# CurvedThumbs.net
KiCad netlist of a schematic drawn in EAGLE
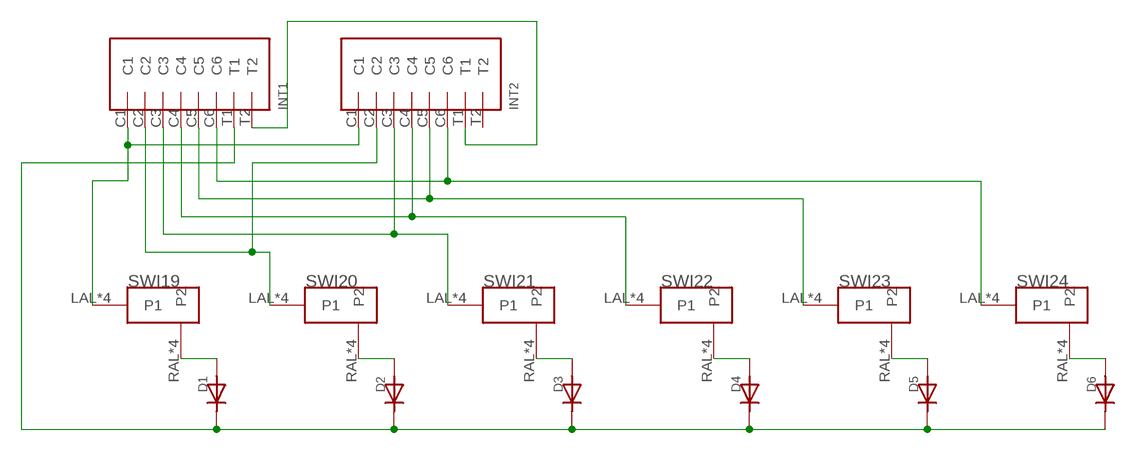
[diagram p0: schematic, sheet 1]

(export (version "E")
  (design (tool "Eeschema 10.0.6"))
  (components
    (comp (ref "D1")
      (value "DIODE")
      (footprint "eagle-import:DIODE_COMBO")
      (libsource (lib "eagle-import") (part "DIODE"))
    )
    (comp (ref "D2")
      (value "DIODE")
      (footprint "eagle-import:DIODE_COMBO")
      (libsource (lib "eagle-import") (part "DIODE"))
    )
    (comp (ref "D3")
      (value "DIODE")
      (footprint "eagle-import:DIODE_COMBO")
      (libsource (lib "eagle-import") (part "DIODE"))
    )
    (comp (ref "D4")
      (value "DIODE")
      (footprint "eagle-import:DIODE_COMBO")
      (libsource (lib "eagle-import") (part "DIODE"))
    )
    (comp (ref "D5")
      (value "DIODE")
      (footprint "eagle-import:DIODE_COMBO")
      (libsource (lib "eagle-import") (part "DIODE"))
    )
    (comp (ref "D6")
      (value "DIODE")
      (footprint "eagle-import:DIODE_COMBO")
      (libsource (lib "eagle-import") (part "DIODE"))
    )
    (comp (ref "INT1")
      (value "INTRCNNT")
      (footprint "eagle-import:INTRCNNT")
      (libsource (lib "eagle-import") (part "INTRCNNT"))
    )
    (comp (ref "INT2")
      (value "INTRCNNT")
      (footprint "eagle-import:INTRCNNT")
      (libsource (lib "eagle-import") (part "INTRCNNT"))
    )
    (comp (ref "SWI19")
      (value "MX/ALPSDOUBLESIDED")
      (footprint "eagle-import:DOUBLED_MX_ALPS")
      (libsource (lib "eagle-import") (part "MX/ALPSDOUBLESIDED"))
    )
    (comp (ref "SWI20")
      (value "MX/ALPSDOUBLESIDED")
      (footprint "eagle-import:DOUBLED_MX_ALPS")
      (libsource (lib "eagle-import") (part "MX/ALPSDOUBLESIDED"))
    )
    (comp (ref "SWI21")
      (value "MX/ALPSDOUBLESIDED")
      (footprint "eagle-import:DOUBLED_MX_ALPS")
      (libsource (lib "eagle-import") (part "MX/ALPSDOUBLESIDED"))
    )
    (comp (ref "SWI22")
      (value "MX/ALPSDOUBLESIDED")
      (footprint "eagle-import:DOUBLED_MX_ALPS")
      (libsource (lib "eagle-import") (part "MX/ALPSDOUBLESIDED"))
    )
    (comp (ref "SWI23")
      (value "MX/ALPSDOUBLESIDED")
      (footprint "eagle-import:DOUBLED_MX_ALPS")
      (libsource (lib "eagle-import") (part "MX/ALPSDOUBLESIDED"))
    )
    (comp (ref "SWI24")
      (value "MX/ALPSDOUBLESIDED")
      (footprint "eagle-import:DOUBLED_MX_ALPS")
      (libsource (lib "eagle-import") (part "MX/ALPSDOUBLESIDED"))
    )
  )
  (nets
    (net (code "1") (name "Net-(D1-AN-PadANOSB)") (class "Default")
      (node (ref "D1") (pin "ANOSB") (pinfunction "AN_ANOSB") (pintype "bidirectional"))
      (node (ref "D1") (pin "ANOST") (pinfunction "AN_ANOST") (pintype "bidirectional"))
      (node (ref "D1") (pin "ANOT") (pinfunction "AN_ANOT") (pintype "bidirectional"))
      (node (ref "SWI19") (pin "RAL") (pinfunction "P2_RAL") (pintype "bidirectional"))
      (node (ref "SWI19") (pin "RAR") (pinfunction "P2_RAR") (pintype "bidirectional"))
      (node (ref "SWI19") (pin "RCL") (pinfunction "P2_RCL") (pintype "bidirectional"))
      (node (ref "SWI19") (pin "RCR") (pinfunction "P2_RCR") (pintype "bidirectional"))
    )
    (net (code "2") (name "Net-(D1-CAT-PadCATSB)") (class "Default")
      (node (ref "D1") (pin "CATSB") (pinfunction "CAT_CATSB") (pintype "bidirectional"))
      (node (ref "D1") (pin "CATST") (pinfunction "CAT_CATST") (pintype "bidirectional"))
      (node (ref "D1") (pin "CATT") (pinfunction "CAT_CATT") (pintype "bidirectional"))
      (node (ref "D2") (pin "CATSB") (pinfunction "CAT_CATSB") (pintype "bidirectional"))
      (node (ref "D2") (pin "CATST") (pinfunction "CAT_CATST") (pintype "bidirectional"))
      (node (ref "D2") (pin "CATT") (pinfunction "CAT_CATT") (pintype "bidirectional"))
      (node (ref "D3") (pin "CATSB") (pinfunction "CAT_CATSB") (pintype "bidirectional"))
      (node (ref "D3") (pin "CATST") (pinfunction "CAT_CATST") (pintype "bidirectional"))
      (node (ref "D3") (pin "CATT") (pinfunction "CAT_CATT") (pintype "bidirectional"))
      (node (ref "D4") (pin "CATSB") (pinfunction "CAT_CATSB") (pintype "bidirectional"))
      (node (ref "D4") (pin "CATST") (pinfunction "CAT_CATST") (pintype "bidirectional"))
      (node (ref "D4") (pin "CATT") (pinfunction "CAT_CATT") (pintype "bidirectional"))
      (node (ref "D5") (pin "CATSB") (pinfunction "CAT_CATSB") (pintype "bidirectional"))
      (node (ref "D5") (pin "CATST") (pinfunction "CAT_CATST") (pintype "bidirectional"))
      (node (ref "D5") (pin "CATT") (pinfunction "CAT_CATT") (pintype "bidirectional"))
      (node (ref "D6") (pin "CATSB") (pinfunction "CAT_CATSB") (pintype "bidirectional"))
      (node (ref "D6") (pin "CATST") (pinfunction "CAT_CATST") (pintype "bidirectional"))
      (node (ref "D6") (pin "CATT") (pinfunction "CAT_CATT") (pintype "bidirectional"))
      (node (ref "INT1") (pin "T1") (pinfunction "T1_T1") (pintype "bidirectional"))
    )
    (net (code "3") (name "Net-(D2-AN-PadANOSB)") (class "Default")
      (node (ref "D2") (pin "ANOSB") (pinfunction "AN_ANOSB") (pintype "bidirectional"))
      (node (ref "D2") (pin "ANOST") (pinfunction "AN_ANOST") (pintype "bidirectional"))
      (node (ref "D2") (pin "ANOT") (pinfunction "AN_ANOT") (pintype "bidirectional"))
      (node (ref "SWI20") (pin "RAL") (pinfunction "P2_RAL") (pintype "bidirectional"))
      (node (ref "SWI20") (pin "RAR") (pinfunction "P2_RAR") (pintype "bidirectional"))
      (node (ref "SWI20") (pin "RCL") (pinfunction "P2_RCL") (pintype "bidirectional"))
      (node (ref "SWI20") (pin "RCR") (pinfunction "P2_RCR") (pintype "bidirectional"))
    )
    (net (code "4") (name "Net-(D3-AN-PadANOSB)") (class "Default")
      (node (ref "D3") (pin "ANOSB") (pinfunction "AN_ANOSB") (pintype "bidirectional"))
      (node (ref "D3") (pin "ANOST") (pinfunction "AN_ANOST") (pintype "bidirectional"))
      (node (ref "D3") (pin "ANOT") (pinfunction "AN_ANOT") (pintype "bidirectional"))
      (node (ref "SWI21") (pin "RAL") (pinfunction "P2_RAL") (pintype "bidirectional"))
      (node (ref "SWI21") (pin "RAR") (pinfunction "P2_RAR") (pintype "bidirectional"))
      (node (ref "SWI21") (pin "RCL") (pinfunction "P2_RCL") (pintype "bidirectional"))
      (node (ref "SWI21") (pin "RCR") (pinfunction "P2_RCR") (pintype "bidirectional"))
    )
    (net (code "5") (name "Net-(D4-AN-PadANOSB)") (class "Default")
      (node (ref "D4") (pin "ANOSB") (pinfunction "AN_ANOSB") (pintype "bidirectional"))
      (node (ref "D4") (pin "ANOST") (pinfunction "AN_ANOST") (pintype "bidirectional"))
      (node (ref "D4") (pin "ANOT") (pinfunction "AN_ANOT") (pintype "bidirectional"))
      (node (ref "SWI22") (pin "RAL") (pinfunction "P2_RAL") (pintype "bidirectional"))
      (node (ref "SWI22") (pin "RAR") (pinfunction "P2_RAR") (pintype "bidirectional"))
      (node (ref "SWI22") (pin "RCL") (pinfunction "P2_RCL") (pintype "bidirectional"))
      (node (ref "SWI22") (pin "RCR") (pinfunction "P2_RCR") (pintype "bidirectional"))
    )
    (net (code "6") (name "Net-(D5-AN-PadANOSB)") (class "Default")
      (node (ref "D5") (pin "ANOSB") (pinfunction "AN_ANOSB") (pintype "bidirectional"))
      (node (ref "D5") (pin "ANOST") (pinfunction "AN_ANOST") (pintype "bidirectional"))
      (node (ref "D5") (pin "ANOT") (pinfunction "AN_ANOT") (pintype "bidirectional"))
      (node (ref "SWI23") (pin "RAL") (pinfunction "P2_RAL") (pintype "bidirectional"))
      (node (ref "SWI23") (pin "RAR") (pinfunction "P2_RAR") (pintype "bidirectional"))
      (node (ref "SWI23") (pin "RCL") (pinfunction "P2_RCL") (pintype "bidirectional"))
      (node (ref "SWI23") (pin "RCR") (pinfunction "P2_RCR") (pintype "bidirectional"))
    )
    (net (code "7") (name "Net-(D6-AN-PadANOSB)") (class "Default")
      (node (ref "D6") (pin "ANOSB") (pinfunction "AN_ANOSB") (pintype "bidirectional"))
      (node (ref "D6") (pin "ANOST") (pinfunction "AN_ANOST") (pintype "bidirectional"))
      (node (ref "D6") (pin "ANOT") (pinfunction "AN_ANOT") (pintype "bidirectional"))
      (node (ref "SWI24") (pin "RAL") (pinfunction "P2_RAL") (pintype "bidirectional"))
      (node (ref "SWI24") (pin "RAR") (pinfunction "P2_RAR") (pintype "bidirectional"))
      (node (ref "SWI24") (pin "RCL") (pinfunction "P2_RCL") (pintype "bidirectional"))
      (node (ref "SWI24") (pin "RCR") (pinfunction "P2_RCR") (pintype "bidirectional"))
    )
    (net (code "8") (name "Net-(INT1-PadC1)") (class "Default")
      (node (ref "INT1") (pin "C1") (pinfunction "C1_C1") (pintype "bidirectional"))
      (node (ref "INT2") (pin "C1") (pinfunction "C1_C1") (pintype "bidirectional"))
      (node (ref "SWI19") (pin "LAL") (pinfunction "P1_LAL") (pintype "bidirectional"))
      (node (ref "SWI19") (pin "LAR") (pinfunction "P1_LAR") (pintype "bidirectional"))
      (node (ref "SWI19") (pin "LCL") (pinfunction "P1_LCL") (pintype "bidirectional"))
      (node (ref "SWI19") (pin "LCR") (pinfunction "P1_LCR") (pintype "bidirectional"))
    )
    (net (code "9") (name "Net-(INT1-PadC2)") (class "Default")
      (node (ref "INT1") (pin "C2") (pinfunction "C2_C2") (pintype "bidirectional"))
      (node (ref "INT2") (pin "C2") (pinfunction "C2_C2") (pintype "bidirectional"))
      (node (ref "SWI20") (pin "LAL") (pinfunction "P1_LAL") (pintype "bidirectional"))
      (node (ref "SWI20") (pin "LAR") (pinfunction "P1_LAR") (pintype "bidirectional"))
      (node (ref "SWI20") (pin "LCL") (pinfunction "P1_LCL") (pintype "bidirectional"))
      (node (ref "SWI20") (pin "LCR") (pinfunction "P1_LCR") (pintype "bidirectional"))
    )
    (net (code "10") (name "Net-(INT1-PadC3)") (class "Default")
      (node (ref "INT1") (pin "C3") (pinfunction "C3_C3") (pintype "bidirectional"))
      (node (ref "INT2") (pin "C3") (pinfunction "C3_C3") (pintype "bidirectional"))
      (node (ref "SWI21") (pin "LAL") (pinfunction "P1_LAL") (pintype "bidirectional"))
      (node (ref "SWI21") (pin "LAR") (pinfunction "P1_LAR") (pintype "bidirectional"))
      (node (ref "SWI21") (pin "LCL") (pinfunction "P1_LCL") (pintype "bidirectional"))
      (node (ref "SWI21") (pin "LCR") (pinfunction "P1_LCR") (pintype "bidirectional"))
    )
    (net (code "11") (name "Net-(INT1-PadC4)") (class "Default")
      (node (ref "INT1") (pin "C4") (pinfunction "C4_C4") (pintype "bidirectional"))
      (node (ref "INT2") (pin "C4") (pinfunction "C4_C4") (pintype "bidirectional"))
      (node (ref "SWI22") (pin "LAL") (pinfunction "P1_LAL") (pintype "bidirectional"))
      (node (ref "SWI22") (pin "LAR") (pinfunction "P1_LAR") (pintype "bidirectional"))
      (node (ref "SWI22") (pin "LCL") (pinfunction "P1_LCL") (pintype "bidirectional"))
      (node (ref "SWI22") (pin "LCR") (pinfunction "P1_LCR") (pintype "bidirectional"))
    )
    (net (code "12") (name "Net-(INT1-PadC5)") (class "Default")
      (node (ref "INT1") (pin "C5") (pinfunction "C5_C5") (pintype "bidirectional"))
      (node (ref "INT2") (pin "C5") (pinfunction "C5_C5") (pintype "bidirectional"))
      (node (ref "SWI23") (pin "LAL") (pinfunction "P1_LAL") (pintype "bidirectional"))
      (node (ref "SWI23") (pin "LAR") (pinfunction "P1_LAR") (pintype "bidirectional"))
      (node (ref "SWI23") (pin "LCL") (pinfunction "P1_LCL") (pintype "bidirectional"))
      (node (ref "SWI23") (pin "LCR") (pinfunction "P1_LCR") (pintype "bidirectional"))
    )
    (net (code "13") (name "Net-(INT1-PadC6)") (class "Default")
      (node (ref "INT1") (pin "C6") (pinfunction "C6_C6") (pintype "bidirectional"))
      (node (ref "INT2") (pin "C6") (pinfunction "C6_C6") (pintype "bidirectional"))
      (node (ref "SWI24") (pin "LAL") (pinfunction "P1_LAL") (pintype "bidirectional"))
      (node (ref "SWI24") (pin "LAR") (pinfunction "P1_LAR") (pintype "bidirectional"))
      (node (ref "SWI24") (pin "LCL") (pinfunction "P1_LCL") (pintype "bidirectional"))
      (node (ref "SWI24") (pin "LCR") (pinfunction "P1_LCR") (pintype "bidirectional"))
    )
    (net (code "14") (name "Net-(INT1-PadT2)") (class "Default")
      (node (ref "INT1") (pin "T2") (pinfunction "T2_T2") (pintype "bidirectional"))
      (node (ref "INT2") (pin "T1") (pinfunction "T1_T1") (pintype "bidirectional"))
    )
    (net (code "15") (name "unconnected-(INT2-PadT2)") (class "Default")
      (node (ref "INT2") (pin "T2") (pinfunction "T2_T2") (pintype "bidirectional"))
    )
  )
)
